# KMO_IO_MV2_5.net
KiCad netlist of a schematic drawn in EAGLE
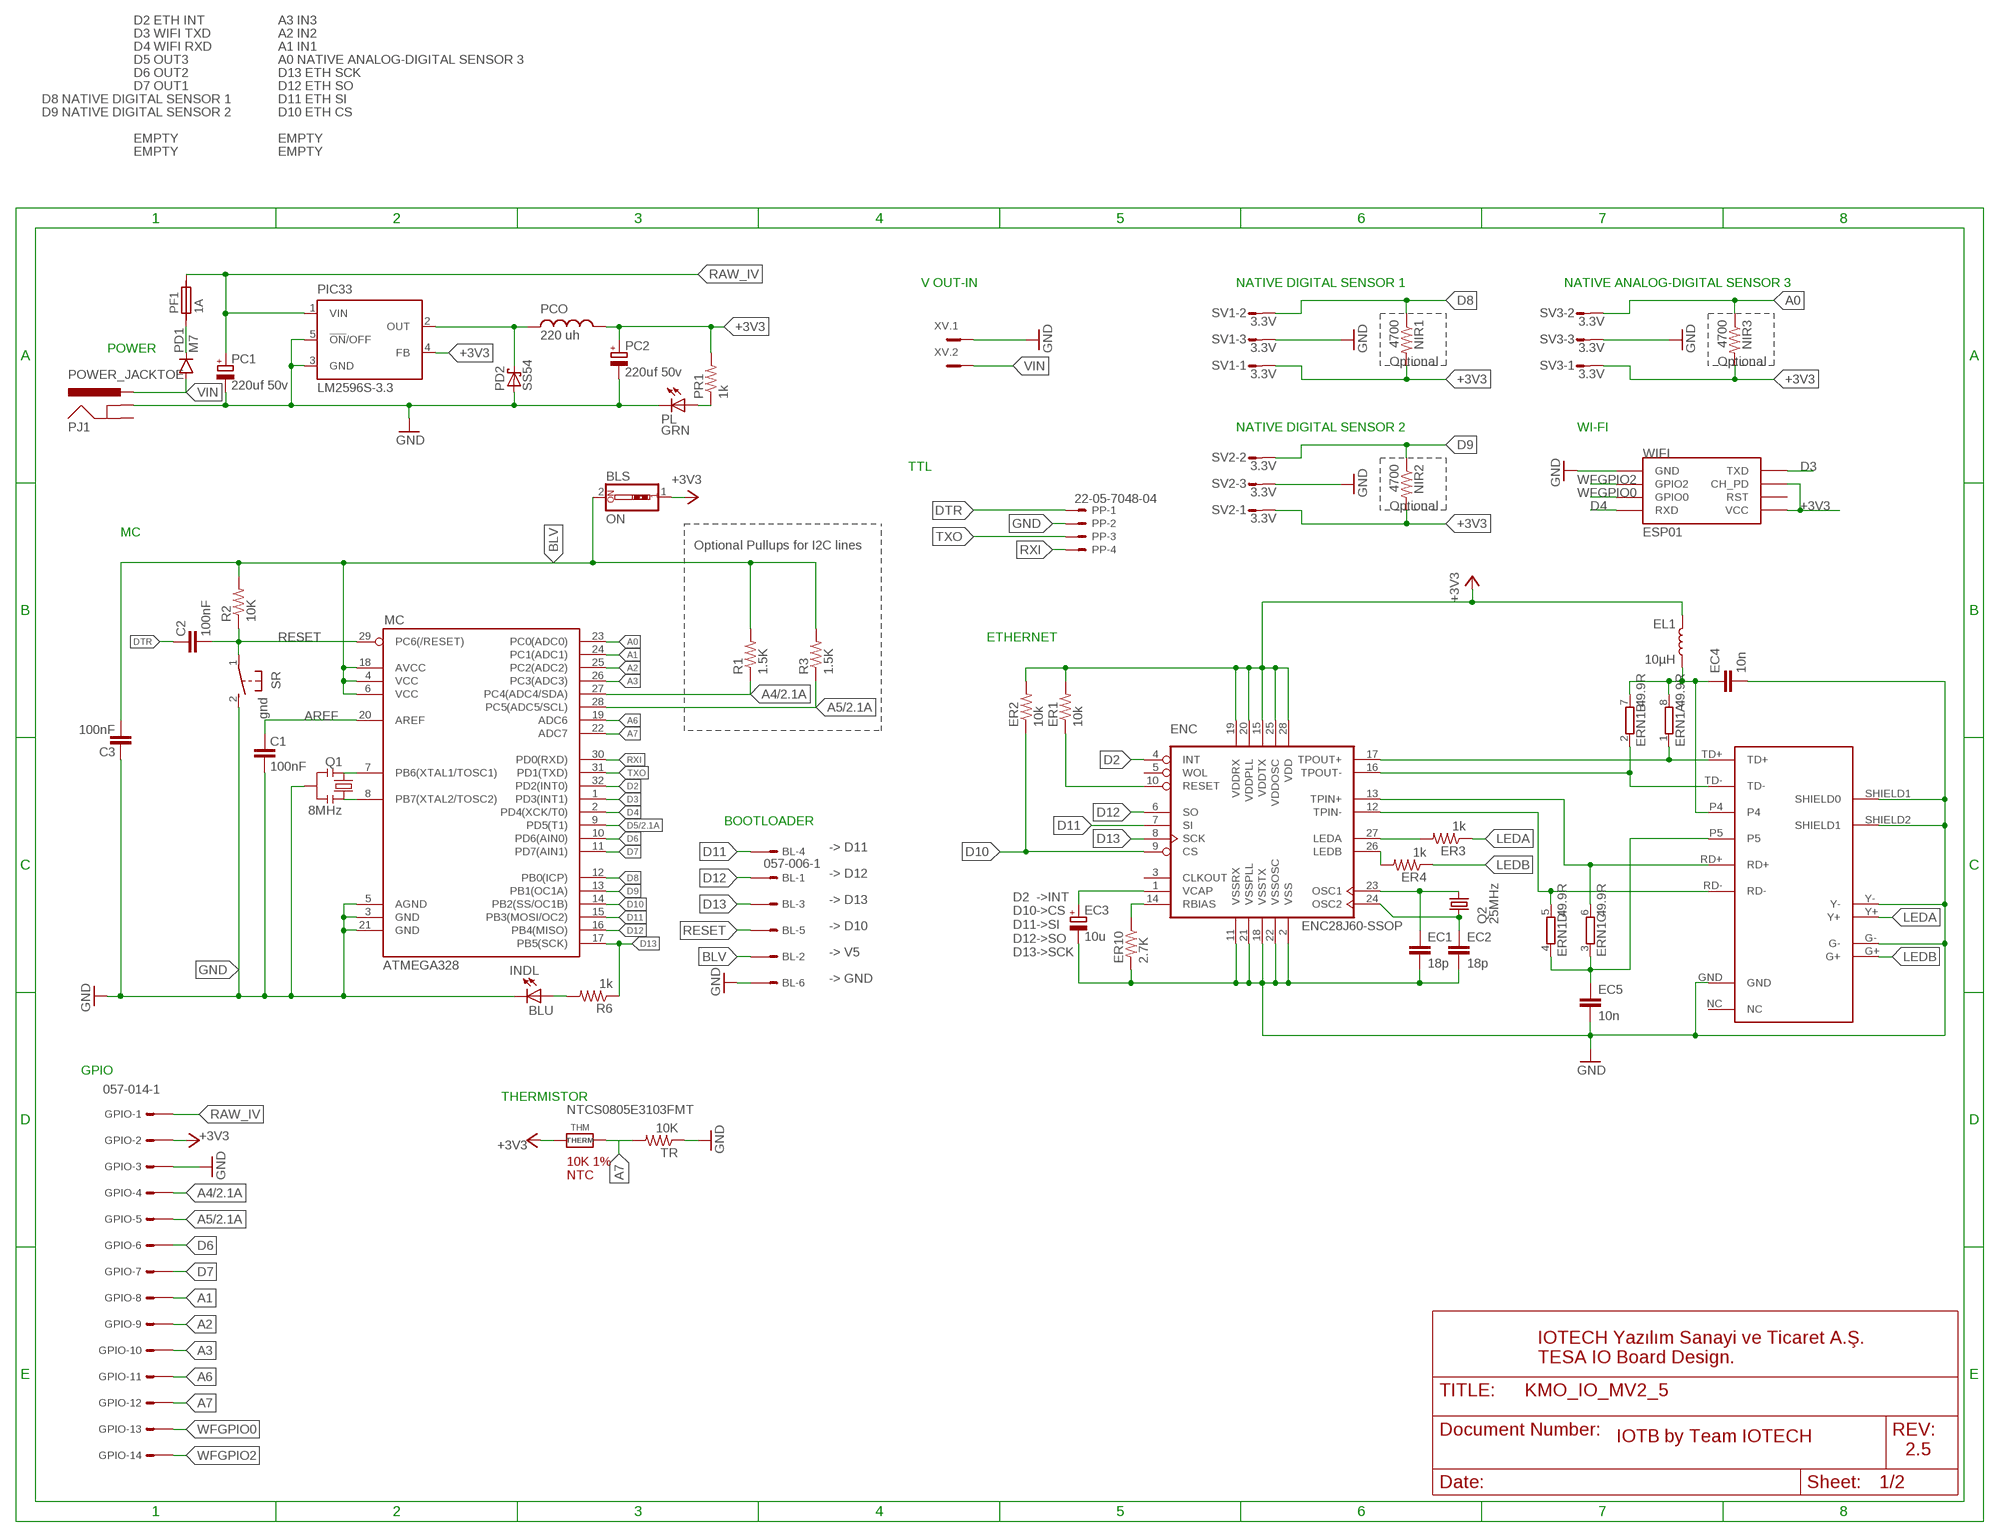
[diagram p0: schematic, sheet 1]
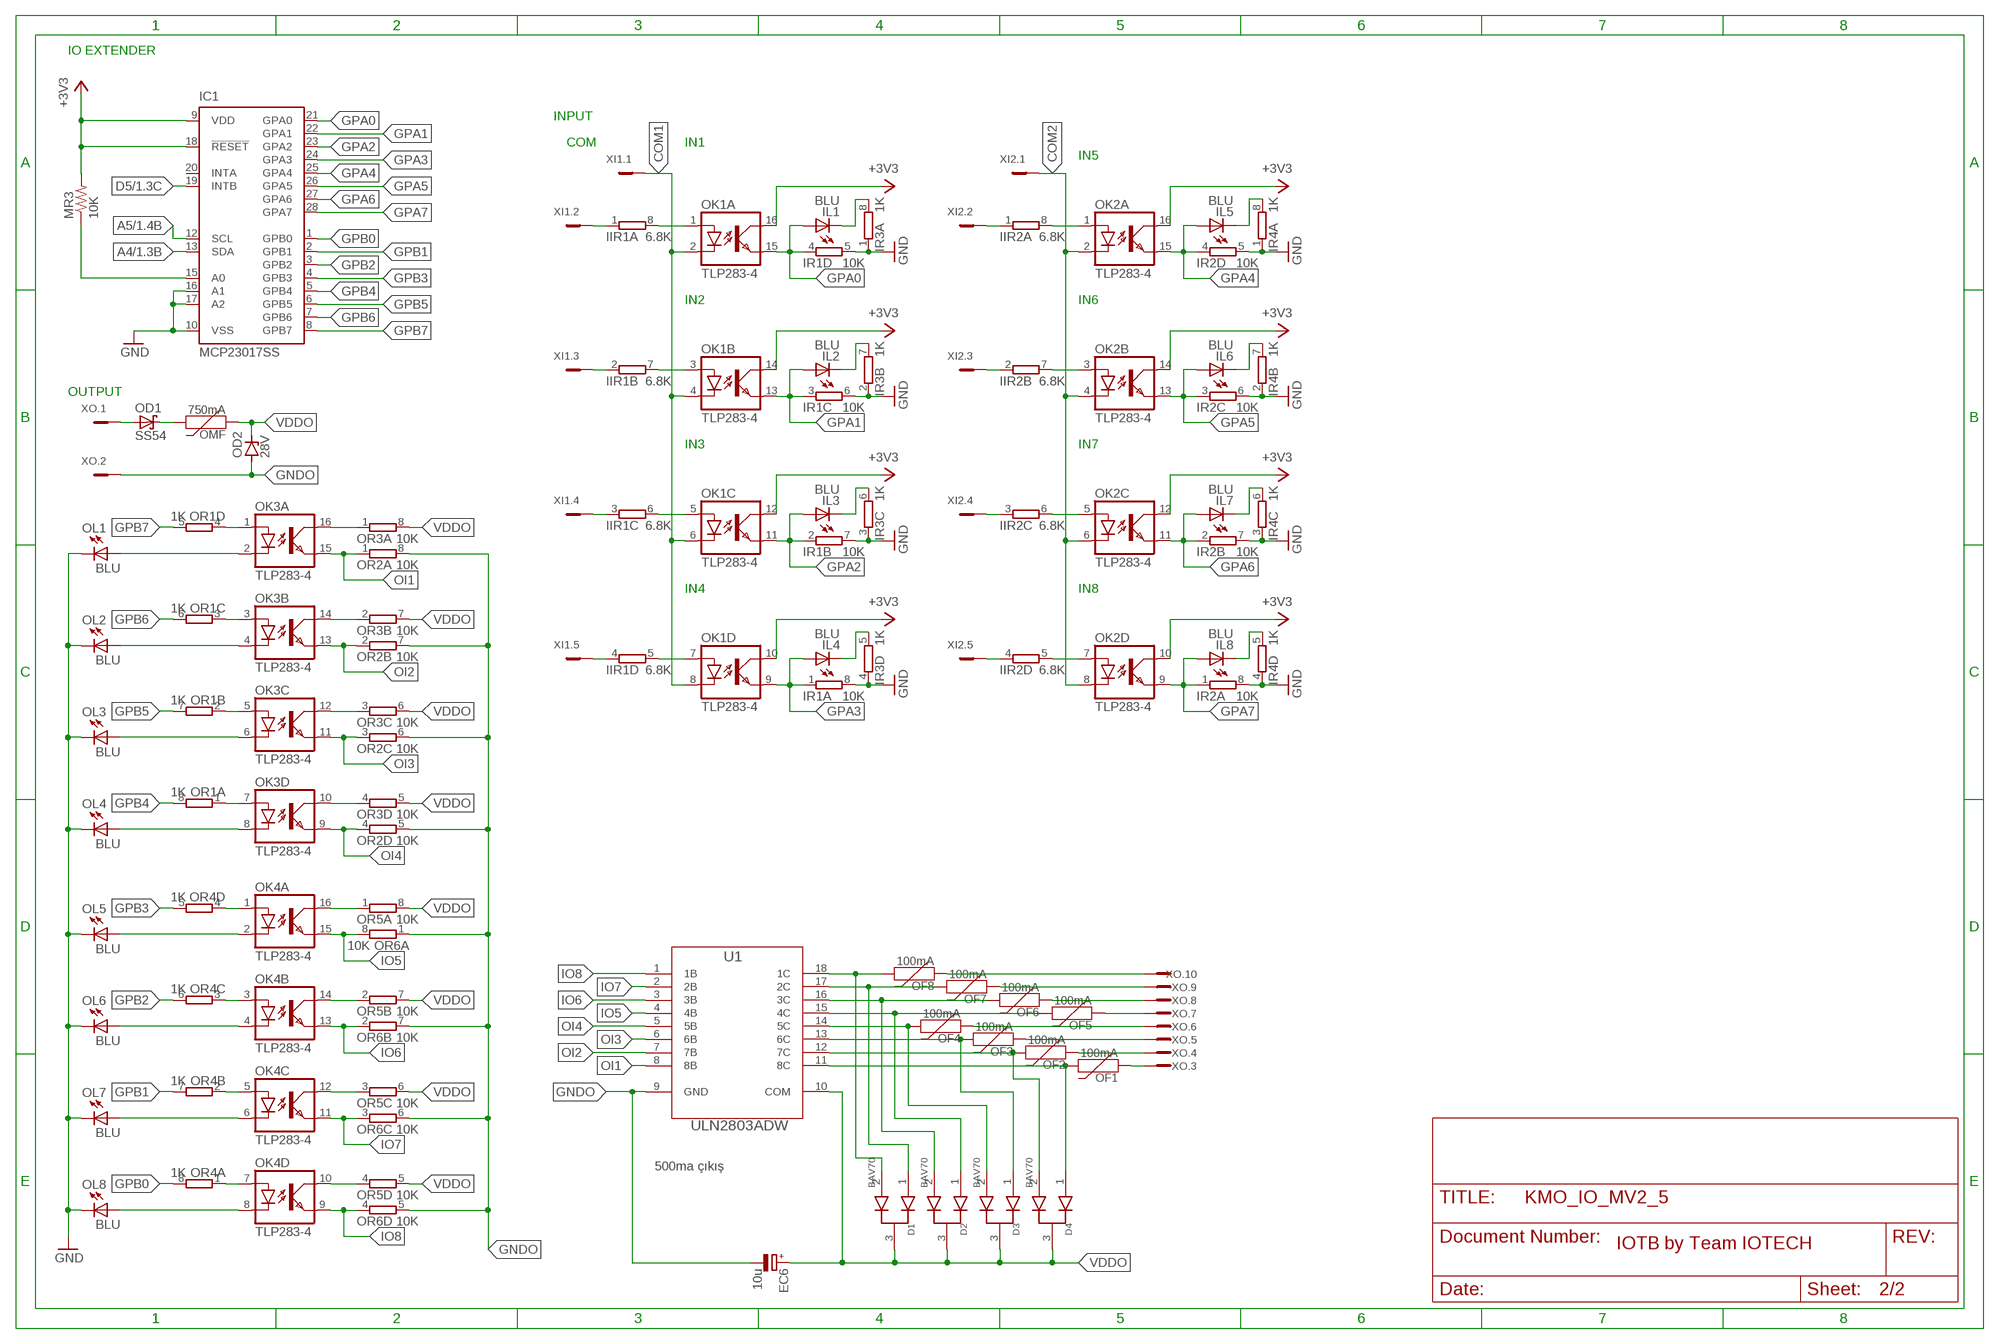
[diagram p1: schematic, sheet 2]

(export (version "E")
  (design (tool "Eeschema 10.0.6"))
  (components
    (comp (ref "D1")
      (value "BAV70")
      (footprint "eagle-import:SOT-23-3")
      (fields (field (name "MF") "Multicomp") (field (name "MP") "BAV70+"))
      (libsource (lib "eagle-import") (part "BAV70"))
    )
    (comp (ref "D2")
      (value "BAV70")
      (footprint "eagle-import:SOT-23-3")
      (fields (field (name "MF") "Multicomp") (field (name "MP") "BAV70+"))
      (libsource (lib "eagle-import") (part "BAV70"))
    )
    (comp (ref "D3")
      (value "BAV70")
      (footprint "eagle-import:SOT-23-3")
      (fields (field (name "MF") "Multicomp") (field (name "MP") "BAV70+"))
      (libsource (lib "eagle-import") (part "BAV70"))
    )
    (comp (ref "D4")
      (value "BAV70")
      (footprint "eagle-import:SOT-23-3")
      (fields (field (name "MF") "Multicomp") (field (name "MP") "BAV70+"))
      (libsource (lib "eagle-import") (part "BAV70"))
    )
    (comp (ref "EC6")
      (value "10u")
      (footprint "eagle-import:CT3216")
      (libsource (lib "eagle-import") (part "CPOL-EUCT3216"))
    )
    (comp (ref "IC1")
      (value "MCP23017SS")
      (footprint "eagle-import:SSOP28")
      (fields (field (name "MF") "MICROCHIP") (field (name "MPN") "MCP23017-E/SS"))
      (libsource (lib "eagle-import") (part "MCP23017SS"))
    )
    (comp (ref "IIR1")
      (value "6.8K")
      (footprint "eagle-import:0603-ARV")
      (libsource (lib "eagle-import") (part "4R-N0603-ARV"))
    )
    (comp (ref "IIR2")
      (value "6.8K")
      (footprint "eagle-import:0603-ARV")
      (libsource (lib "eagle-import") (part "4R-N0603-ARV"))
    )
    (comp (ref "IL1")
      (value "BLU")
      (footprint "eagle-import:CHIP-LED0805")
      (libsource (lib "eagle-import") (part "LEDCHIP-LED0805"))
    )
    (comp (ref "IL2")
      (value "BLU")
      (footprint "eagle-import:CHIP-LED0805")
      (libsource (lib "eagle-import") (part "LEDCHIP-LED0805"))
    )
    (comp (ref "IL3")
      (value "BLU")
      (footprint "eagle-import:CHIP-LED0805")
      (libsource (lib "eagle-import") (part "LEDCHIP-LED0805"))
    )
    (comp (ref "IL4")
      (value "BLU")
      (footprint "eagle-import:CHIP-LED0805")
      (libsource (lib "eagle-import") (part "LEDCHIP-LED0805"))
    )
    (comp (ref "IL5")
      (value "BLU")
      (footprint "eagle-import:CHIP-LED0805")
      (libsource (lib "eagle-import") (part "LEDCHIP-LED0805"))
    )
    (comp (ref "IL6")
      (value "BLU")
      (footprint "eagle-import:CHIP-LED0805")
      (libsource (lib "eagle-import") (part "LEDCHIP-LED0805"))
    )
    (comp (ref "IL7")
      (value "BLU")
      (footprint "eagle-import:CHIP-LED0805")
      (libsource (lib "eagle-import") (part "LEDCHIP-LED0805"))
    )
    (comp (ref "IL8")
      (value "BLU")
      (footprint "eagle-import:CHIP-LED0805")
      (libsource (lib "eagle-import") (part "LEDCHIP-LED0805"))
    )
    (comp (ref "IR1")
      (value "10K")
      (footprint "eagle-import:0603-ARV")
      (libsource (lib "eagle-import") (part "4R-N0603-ARV"))
    )
    (comp (ref "IR2")
      (value "10K")
      (footprint "eagle-import:0603-ARV")
      (libsource (lib "eagle-import") (part "4R-N0603-ARV"))
    )
    (comp (ref "IR3")
      (value "1K")
      (footprint "eagle-import:0603-ARV")
      (libsource (lib "eagle-import") (part "4R-N0603-ARV"))
    )
    (comp (ref "IR4")
      (value "1K")
      (footprint "eagle-import:0603-ARV")
      (libsource (lib "eagle-import") (part "4R-N0603-ARV"))
    )
    (comp (ref "MR3")
      (value "10K")
      (footprint "eagle-import:0805")
      (libsource (lib "eagle-import") (part "RESISTOR0805-RES"))
    )
    (comp (ref "OD1")
      (value "SS54")
      (footprint "eagle-import:SMB")
      (libsource (lib "eagle-import") (part "SCHOTTKY-DIODESMD"))
    )
    (comp (ref "OD2")
      (value "28V")
      (footprint "eagle-import:SMB")
      (libsource (lib "eagle-import") (part "ZENER-DIODESMB"))
    )
    (comp (ref "OF1")
      (value "100mA")
      (footprint "eagle-import:1206")
      (libsource (lib "eagle-import") (part "PPTC_0.75A"))
    )
    (comp (ref "OF2")
      (value "100mA")
      (footprint "eagle-import:1206")
      (libsource (lib "eagle-import") (part "PPTC_0.75A"))
    )
    (comp (ref "OF3")
      (value "100mA")
      (footprint "eagle-import:1206")
      (libsource (lib "eagle-import") (part "PPTC_0.75A"))
    )
    (comp (ref "OF4")
      (value "100mA")
      (footprint "eagle-import:1206")
      (libsource (lib "eagle-import") (part "PPTC_0.75A"))
    )
    (comp (ref "OF5")
      (value "100mA")
      (footprint "eagle-import:1206")
      (libsource (lib "eagle-import") (part "PPTC_0.75A"))
    )
    (comp (ref "OF6")
      (value "100mA")
      (footprint "eagle-import:1206")
      (libsource (lib "eagle-import") (part "PPTC_0.75A"))
    )
    (comp (ref "OF7")
      (value "100mA")
      (footprint "eagle-import:1206")
      (libsource (lib "eagle-import") (part "PPTC_0.75A"))
    )
    (comp (ref "OF8")
      (value "100mA")
      (footprint "eagle-import:1206")
      (libsource (lib "eagle-import") (part "PPTC_0.75A"))
    )
    (comp (ref "OK1")
      (value "TLP283-4")
      (footprint "eagle-import:MINI-FLAT-16")
      (fields (field (name "SPICEPREFIX") "O"))
      (libsource (lib "eagle-import") (part "TLP283-4"))
    )
    (comp (ref "OK2")
      (value "TLP283-4")
      (footprint "eagle-import:MINI-FLAT-16")
      (fields (field (name "SPICEPREFIX") "O"))
      (libsource (lib "eagle-import") (part "TLP283-4"))
    )
    (comp (ref "OK3")
      (value "TLP283-4")
      (footprint "eagle-import:MINI-FLAT-16")
      (libsource (lib "eagle-import") (part "TLP283-4"))
    )
    (comp (ref "OK4")
      (value "TLP283-4")
      (footprint "eagle-import:MINI-FLAT-16")
      (libsource (lib "eagle-import") (part "TLP283-4"))
    )
    (comp (ref "OL1")
      (value "BLU")
      (footprint "eagle-import:CHIP-LED0805")
      (libsource (lib "eagle-import") (part "LEDCHIP-LED0805"))
    )
    (comp (ref "OL2")
      (value "BLU")
      (footprint "eagle-import:CHIP-LED0805")
      (libsource (lib "eagle-import") (part "LEDCHIP-LED0805"))
    )
    (comp (ref "OL3")
      (value "BLU")
      (footprint "eagle-import:CHIP-LED0805")
      (libsource (lib "eagle-import") (part "LEDCHIP-LED0805"))
    )
    (comp (ref "OL4")
      (value "BLU")
      (footprint "eagle-import:CHIP-LED0805")
      (libsource (lib "eagle-import") (part "LEDCHIP-LED0805"))
    )
    (comp (ref "OL5")
      (value "BLU")
      (footprint "eagle-import:CHIP-LED0805")
      (libsource (lib "eagle-import") (part "LEDCHIP-LED0805"))
    )
    (comp (ref "OL6")
      (value "BLU")
      (footprint "eagle-import:CHIP-LED0805")
      (libsource (lib "eagle-import") (part "LEDCHIP-LED0805"))
    )
    (comp (ref "OL7")
      (value "BLU")
      (footprint "eagle-import:CHIP-LED0805")
      (libsource (lib "eagle-import") (part "LEDCHIP-LED0805"))
    )
    (comp (ref "OL8")
      (value "BLU")
      (footprint "eagle-import:CHIP-LED0805")
      (libsource (lib "eagle-import") (part "LEDCHIP-LED0805"))
    )
    (comp (ref "OMF")
      (value "750mA")
      (footprint "eagle-import:1206")
      (libsource (lib "eagle-import") (part "PPTC_0.75A"))
    )
    (comp (ref "OR1")
      (value "1K")
      (footprint "eagle-import:0603-ARV")
      (libsource (lib "eagle-import") (part "4R-N0603-ARV"))
    )
    (comp (ref "OR2")
      (value "10K")
      (footprint "eagle-import:0603-ARV")
      (libsource (lib "eagle-import") (part "4R-N0603-ARV"))
    )
    (comp (ref "OR3")
      (value "10K")
      (footprint "eagle-import:0603-ARV")
      (libsource (lib "eagle-import") (part "4R-N0603-ARV"))
    )
    (comp (ref "OR4")
      (value "1K")
      (footprint "eagle-import:0603-ARV")
      (libsource (lib "eagle-import") (part "4R-N0603-ARV"))
    )
    (comp (ref "OR5")
      (value "10K")
      (footprint "eagle-import:0603-ARV")
      (libsource (lib "eagle-import") (part "4R-N0603-ARV"))
    )
    (comp (ref "OR6")
      (value "10K")
      (footprint "eagle-import:0603-ARV")
      (libsource (lib "eagle-import") (part "4R-N0603-ARV"))
    )
    (comp (ref "U1")
      (value "ULN2803ADW")
      (footprint "eagle-import:SOIC127P1030X265-18N")
      (libsource (lib "eagle-import") (part "ULN2803ADW"))
    )
    (comp (ref "XI1")
      (value "MC5")
      (footprint "eagle-import:MC5")
      (libsource (lib "eagle-import") (part "MC5"))
    )
    (comp (ref "XI2")
      (value "MC5")
      (footprint "eagle-import:MC5")
      (libsource (lib "eagle-import") (part "MC5"))
    )
    (comp (ref "XO")
      (value "MC10")
      (footprint "eagle-import:MC10")
      (libsource (lib "eagle-import") (part "MC10"))
    )
    (comp (ref "BL")
      (value "057-006-1")
      (footprint "eagle-import:057-006-1")
      (libsource (lib "eagle-import") (part "057-006-1"))
    )
    (comp (ref "BLS")
      (value "ON")
      (footprint "eagle-import:EDG-01")
      (libsource (lib "eagle-import") (part "SW_DIP-1"))
    )
    (comp (ref "C1")
      (value "100nF")
      (footprint "eagle-import:0805")
      (libsource (lib "eagle-import") (part "CAP0805"))
    )
    (comp (ref "C2")
      (value "100nF")
      (footprint "eagle-import:0805")
      (libsource (lib "eagle-import") (part "CAP0805"))
    )
    (comp (ref "C3")
      (value "100nF")
      (footprint "eagle-import:0805")
      (libsource (lib "eagle-import") (part "CAP0805"))
    )
    (comp (ref "EC1")
      (value "18p")
      (footprint "eagle-import:0805")
      (libsource (lib "eagle-import") (part "CAP0805"))
    )
    (comp (ref "EC2")
      (value "18p")
      (footprint "eagle-import:0805")
      (libsource (lib "eagle-import") (part "CAP0805"))
    )
    (comp (ref "EC3")
      (value "10u")
      (footprint "eagle-import:CT3216")
      (libsource (lib "eagle-import") (part "CPOL-EUCT3216"))
    )
    (comp (ref "EC4")
      (value "10n")
      (footprint "eagle-import:0805")
      (libsource (lib "eagle-import") (part "CAP0805"))
    )
    (comp (ref "EC5")
      (value "10n")
      (footprint "eagle-import:0805")
      (libsource (lib "eagle-import") (part "CAP0805"))
    )
    (comp (ref "EL1")
      (value "10µH")
      (footprint "eagle-import:0805")
      (libsource (lib "eagle-import") (part "INDUCTOR-0805-3.3UH"))
    )
    (comp (ref "ENC")
      (value "ENC28J60-SSOP")
      (footprint "eagle-import:SSOP28")
      (libsource (lib "eagle-import") (part "ENC28J60-SSOP"))
    )
    (comp (ref "ER1")
      (value "10k")
      (footprint "eagle-import:0805")
      (libsource (lib "eagle-import") (part "RESISTOR0805-RES"))
    )
    (comp (ref "ER2")
      (value "10k")
      (footprint "eagle-import:0805")
      (libsource (lib "eagle-import") (part "RESISTOR0805-RES"))
    )
    (comp (ref "ER3")
      (value "1k")
      (footprint "eagle-import:0805")
      (libsource (lib "eagle-import") (part "RESISTOR0805-RES"))
    )
    (comp (ref "ER4")
      (value "1k")
      (footprint "eagle-import:0805")
      (libsource (lib "eagle-import") (part "RESISTOR0805-RES"))
    )
    (comp (ref "ER10")
      (value "2.7K")
      (footprint "eagle-import:0805")
      (libsource (lib "eagle-import") (part "RESISTOR0805-RES"))
    )
    (comp (ref "ERN1")
      (value "49.9R")
      (footprint "eagle-import:0603-ARV")
      (libsource (lib "eagle-import") (part "4R-N0603-ARV"))
    )
    (comp (ref "GPIO")
      (value "057-014-1")
      (footprint "eagle-import:057-014-1")
      (libsource (lib "eagle-import") (part "057-014-1"))
    )
    (comp (ref "INDL")
      (value "BLU")
      (footprint "eagle-import:CHIP-LED0805")
      (libsource (lib "eagle-import") (part "LEDCHIP-LED0805"))
    )
    (comp (ref "MC")
      (value "ATMEGA328")
      (footprint "eagle-import:TQFP32-08")
      (libsource (lib "eagle-import") (part "ATMEGA168"))
    )
    (comp (ref "NIR1")
      (value "4700")
      (footprint "eagle-import:0805")
      (libsource (lib "eagle-import") (part "RESISTOR0805-RES"))
    )
    (comp (ref "NIR2")
      (value "4700")
      (footprint "eagle-import:0805")
      (libsource (lib "eagle-import") (part "RESISTOR0805-RES"))
    )
    (comp (ref "NIR3")
      (value "4700")
      (footprint "eagle-import:0805")
      (libsource (lib "eagle-import") (part "RESISTOR0805-RES"))
    )
    (comp (ref "PC1")
      (value "220uf 50v")
      (footprint "eagle-import:140CLH-1010")
      (libsource (lib "eagle-import") (part "CPOL-EU140CLH-1010"))
    )
    (comp (ref "PC2")
      (value "220uf 50v")
      (footprint "eagle-import:140CLH-1010")
      (libsource (lib "eagle-import") (part "CPOL-EU140CLH-1010"))
    )
    (comp (ref "PCO")
      (value "220 uh")
      (footprint "eagle-import:MSS1260")
      (libsource (lib "eagle-import") (part "MSS1260"))
    )
    (comp (ref "PD1")
      (value "M7")
      (footprint "eagle-import:SMA-DIODE")
      (libsource (lib "eagle-import") (part "DIODESMA"))
    )
    (comp (ref "PD2")
      (value "SS54")
      (footprint "eagle-import:SMB")
      (libsource (lib "eagle-import") (part "SCHOTTKY-DIODESMD"))
    )
    (comp (ref "PF1")
      (value "1A")
      (footprint "eagle-import:1820")
      (libsource (lib "eagle-import") (part "SIBA194600"))
    )
    (comp (ref "PIC33")
      (value "LM2596S-3.3")
      (footprint "eagle-import:TO263-5")
      (fields
        (field (name "MF") "NATIONAL SEMICONDUCTOR")
        (field (name "MPN") "LM2596S-ADJ/NOPB")
        (field (name "SPICEPREFIX") "X")
      )
      (libsource (lib "eagle-import") (part "LM2596S"))
    )
    (comp (ref "PJ1")
      (value "POWER_JACKTOE")
      (footprint "eagle-import:POWER_JACK_SMD_OVERPASTE_TOE")
      (libsource (lib "eagle-import") (part "POWER_JACKTOE"))
    )
    (comp (ref "PL")
      (value "GRN")
      (footprint "eagle-import:CHIP-LED0805")
      (libsource (lib "eagle-import") (part "LEDCHIP-LED0805"))
    )
    (comp (ref "PP")
      (value "22-05-7048-04")
      (footprint "eagle-import:7395-04")
      (fields (field (name "MF") "MOLEX"))
      (libsource (lib "eagle-import") (part "22-?-0405-7048"))
    )
    (comp (ref "PR1")
      (value "1k")
      (footprint "eagle-import:0805")
      (libsource (lib "eagle-import") (part "RESISTOR0805-RES"))
    )
    (comp (ref "Q1")
      (value "8MHz")
      (footprint "eagle-import:RESONATOR-SMD-1_1")
      (libsource (lib "eagle-import") (part "RESONATOR1{colon}1"))
    )
    (comp (ref "Q2")
      (value "25MHz")
      (footprint "eagle-import:5.0X3.2_2")
      (libsource (lib "eagle-import") (part "KX-9B"))
    )
    (comp (ref "R1")
      (value "1.5K")
      (footprint "eagle-import:0805")
      (libsource (lib "eagle-import") (part "RESISTOR0805-RES"))
    )
    (comp (ref "R2")
      (value "10K")
      (footprint "eagle-import:0805")
      (libsource (lib "eagle-import") (part "RESISTOR0805-RES"))
    )
    (comp (ref "R3")
      (value "1.5K")
      (footprint "eagle-import:0805")
      (libsource (lib "eagle-import") (part "RESISTOR0805-RES"))
    )
    (comp (ref "R6")
      (value "1k")
      (footprint "eagle-import:0805")
      (libsource (lib "eagle-import") (part "RESISTOR0805-RES"))
    )
    (comp (ref "SR")
      (value "gnd")
      (footprint "eagle-import:B3F-31XX")
      (fields (field (name "MPN") "B3F-3100"))
      (libsource (lib "eagle-import") (part "31-XX"))
    )
    (comp (ref "SV1")
      (value "3.3V")
      (footprint "eagle-import:S03P")
      (libsource (lib "eagle-import") (part "S03P"))
    )
    (comp (ref "SV2")
      (value "3.3V")
      (footprint "eagle-import:S03P")
      (libsource (lib "eagle-import") (part "S03P"))
    )
    (comp (ref "SV3")
      (value "3.3V")
      (footprint "eagle-import:S03P")
      (libsource (lib "eagle-import") (part "S03P"))
    )
    (comp (ref "THM")
      (value "THERM")
      (footprint "eagle-import:MICROBUILDER_0805_NOTHERMALS")
      (libsource (lib "eagle-import") (part "MICROBUILDER_RESISTOR0805_NOTHERMALS"))
    )
    (comp (ref "TR")
      (value "10K")
      (footprint "eagle-import:0805")
      (libsource (lib "eagle-import") (part "RESISTOR0805-RES"))
    )
    (comp (ref "U$2")
      (value "HR911105A")
      (footprint "eagle-import:RJ45")
      (libsource (lib "eagle-import") (part "HR911105A"))
    )
    (comp (ref "WIFI")
      (value "ESP01")
      (footprint "eagle-import:ESP01")
      (libsource (lib "eagle-import") (part "ESP01"))
    )
    (comp (ref "XV")
      (value "MC2")
      (footprint "eagle-import:MC2")
      (libsource (lib "eagle-import") (part "MC2"))
    )
  )
  (nets
    (net (code "1") (name "+3V3") (class "Default")
      (node (ref "BLS") (pin "1") (pinfunction "1_1") (pintype "passive"))
      (node (ref "EL1") (pin "1") (pinfunction "1_1") (pintype "passive"))
      (node (ref "ENC") (pin "15") (pinfunction "VDDTX_15") (pintype "power_in"))
      (node (ref "ENC") (pin "19") (pinfunction "VDDRX_19") (pintype "power_in"))
      (node (ref "ENC") (pin "20") (pinfunction "VDDPLL_20") (pintype "power_in"))
      (node (ref "ENC") (pin "25") (pinfunction "VDDOSC_25") (pintype "power_in"))
      (node (ref "ENC") (pin "28") (pinfunction "VDD_28") (pintype "power_in"))
      (node (ref "ER1") (pin "2") (pinfunction "2_2") (pintype "passive"))
      (node (ref "ER2") (pin "2") (pinfunction "2_2") (pintype "passive"))
      (node (ref "GPIO") (pin "2") (pinfunction "S_2") (pintype "passive"))
      (node (ref "IC1") (pin "18") (pinfunction "~{RESET}_18") (pintype "input"))
      (node (ref "IC1") (pin "9") (pinfunction "VDD_9") (pintype "power_in"))
      (node (ref "MR3") (pin "2") (pinfunction "2_2") (pintype "passive"))
      (node (ref "NIR1") (pin "2") (pinfunction "2_2") (pintype "passive"))
      (node (ref "NIR2") (pin "2") (pinfunction "2_2") (pintype "passive"))
      (node (ref "NIR3") (pin "2") (pinfunction "2_2") (pintype "passive"))
      (node (ref "OK1") (pin "10") (pinfunction "COL_10") (pintype "passive"))
      (node (ref "OK1") (pin "12") (pinfunction "COL_12") (pintype "passive"))
      (node (ref "OK1") (pin "14") (pinfunction "COL_14") (pintype "passive"))
      (node (ref "OK1") (pin "16") (pinfunction "COL_16") (pintype "passive"))
      (node (ref "OK2") (pin "10") (pinfunction "COL_10") (pintype "passive"))
      (node (ref "OK2") (pin "12") (pinfunction "COL_12") (pintype "passive"))
      (node (ref "OK2") (pin "14") (pinfunction "COL_14") (pintype "passive"))
      (node (ref "OK2") (pin "16") (pinfunction "COL_16") (pintype "passive"))
      (node (ref "PC2") (pin "+") (pinfunction "+_+") (pintype "passive"))
      (node (ref "PCO") (pin "P$1") (pinfunction "P$1_P$1") (pintype "passive"))
      (node (ref "PIC33") (pin "4") (pinfunction "FB_4") (pintype "input"))
      (node (ref "PR1") (pin "2") (pinfunction "2_2") (pintype "passive"))
      (node (ref "SV1") (pin "1") (pinfunction "S_1") (pintype "passive"))
      (node (ref "SV2") (pin "1") (pinfunction "S_1") (pintype "passive"))
      (node (ref "SV3") (pin "1") (pinfunction "S_1") (pintype "passive"))
      (node (ref "THM") (pin "1") (pinfunction "1_1") (pintype "passive"))
      (node (ref "WIFI") (pin "CH_PD") (pinfunction "CH_PD_CH_PD") (pintype "bidirectional"))
      (node (ref "WIFI") (pin "VCC") (pinfunction "VCC_VCC") (pintype "bidirectional"))
    )
    (net (code "2") (name "A0") (class "Default")
      (node (ref "MC") (pin "23") (pinfunction "PC0(ADC0)_23") (pintype "bidirectional"))
      (node (ref "NIR3") (pin "1") (pinfunction "1_1") (pintype "passive"))
      (node (ref "SV3") (pin "2") (pinfunction "S_2") (pintype "passive"))
    )
    (net (code "3") (name "A1") (class "Default")
      (node (ref "GPIO") (pin "8") (pinfunction "S_8") (pintype "passive"))
      (node (ref "MC") (pin "24") (pinfunction "PC1(ADC1)_24") (pintype "bidirectional"))
    )
    (net (code "4") (name "A2") (class "Default")
      (node (ref "GPIO") (pin "9") (pinfunction "S_9") (pintype "passive"))
      (node (ref "MC") (pin "25") (pinfunction "PC2(ADC2)_25") (pintype "bidirectional"))
    )
    (net (code "5") (name "A3") (class "Default")
      (node (ref "GPIO") (pin "10") (pinfunction "S_10") (pintype "passive"))
      (node (ref "MC") (pin "26") (pinfunction "PC3(ADC3)_26") (pintype "bidirectional"))
    )
    (net (code "6") (name "A4") (class "Default")
      (node (ref "GPIO") (pin "4") (pinfunction "S_4") (pintype "passive"))
      (node (ref "IC1") (pin "13") (pinfunction "SDA_13") (pintype "bidirectional"))
      (node (ref "MC") (pin "27") (pinfunction "PC4(ADC4/SDA)_27") (pintype "bidirectional"))
      (node (ref "R1") (pin "1") (pinfunction "1_1") (pintype "passive"))
    )
    (net (code "7") (name "A5") (class "Default")
      (node (ref "GPIO") (pin "5") (pinfunction "S_5") (pintype "passive"))
      (node (ref "IC1") (pin "12") (pinfunction "SCL_12") (pintype "input"))
      (node (ref "MC") (pin "28") (pinfunction "PC5(ADC5/SCL)_28") (pintype "bidirectional"))
      (node (ref "R3") (pin "1") (pinfunction "1_1") (pintype "passive"))
    )
    (net (code "8") (name "A6") (class "Default")
      (node (ref "GPIO") (pin "11") (pinfunction "S_11") (pintype "passive"))
      (node (ref "MC") (pin "19") (pinfunction "ADC6_19") (pintype "bidirectional"))
    )
    (net (code "9") (name "A7") (class "Default")
      (node (ref "GPIO") (pin "12") (pinfunction "S_12") (pintype "passive"))
      (node (ref "MC") (pin "22") (pinfunction "ADC7_22") (pintype "bidirectional"))
      (node (ref "THM") (pin "2") (pinfunction "2_2") (pintype "passive"))
      (node (ref "TR") (pin "2") (pinfunction "2_2") (pintype "passive"))
    )
    (net (code "10") (name "AREF") (class "Default")
      (node (ref "C1") (pin "2") (pinfunction "2_2") (pintype "passive"))
      (node (ref "MC") (pin "20") (pinfunction "AREF_20") (pintype "bidirectional"))
    )
    (net (code "11") (name "BLV") (class "Default")
      (node (ref "BL") (pin "2") (pinfunction "S_2") (pintype "passive"))
      (node (ref "BLS") (pin "2") (pinfunction "2_2") (pintype "passive"))
      (node (ref "C3") (pin "1") (pinfunction "1_1") (pintype "passive"))
      (node (ref "MC") (pin "18") (pinfunction "AVCC_18") (pintype "bidirectional"))
      (node (ref "MC") (pin "4") (pinfunction "VCC_4") (pintype "bidirectional"))
      (node (ref "MC") (pin "6") (pinfunction "VCC_6") (pintype "bidirectional"))
      (node (ref "R1") (pin "2") (pinfunction "2_2") (pintype "passive"))
      (node (ref "R2") (pin "2") (pinfunction "2_2") (pintype "passive"))
      (node (ref "R3") (pin "2") (pinfunction "2_2") (pintype "passive"))
    )
    (net (code "12") (name "COM1") (class "Default")
      (node (ref "OK1") (pin "2") (pinfunction "C_2") (pintype "passive"))
      (node (ref "OK1") (pin "4") (pinfunction "C_4") (pintype "passive"))
      (node (ref "OK1") (pin "6") (pinfunction "C_6") (pintype "passive"))
      (node (ref "OK1") (pin "8") (pinfunction "C_8") (pintype "passive"))
      (node (ref "XI1") (pin "1") (pinfunction "SK_1") (pintype "passive"))
    )
    (net (code "13") (name "COM2") (class "Default")
      (node (ref "OK2") (pin "2") (pinfunction "C_2") (pintype "passive"))
      (node (ref "OK2") (pin "4") (pinfunction "C_4") (pintype "passive"))
      (node (ref "OK2") (pin "6") (pinfunction "C_6") (pintype "passive"))
      (node (ref "OK2") (pin "8") (pinfunction "C_8") (pintype "passive"))
      (node (ref "XI2") (pin "1") (pinfunction "SK_1") (pintype "passive"))
    )
    (net (code "14") (name "D2") (class "Default")
      (node (ref "ENC") (pin "4") (pinfunction "INT_4") (pintype "output"))
      (node (ref "MC") (pin "32") (pinfunction "PD2(INT0)_32") (pintype "bidirectional"))
    )
    (net (code "15") (name "D3") (class "Default")
      (node (ref "MC") (pin "1") (pinfunction "PD3(INT1)_1") (pintype "bidirectional"))
      (node (ref "WIFI") (pin "TX") (pinfunction "TXD_TX") (pintype "bidirectional"))
    )
    (net (code "16") (name "D4") (class "Default")
      (node (ref "MC") (pin "2") (pinfunction "PD4(XCK/T0)_2") (pintype "bidirectional"))
      (node (ref "WIFI") (pin "RX") (pinfunction "RXD_RX") (pintype "bidirectional"))
    )
    (net (code "17") (name "D5") (class "Default")
      (node (ref "IC1") (pin "19") (pinfunction "INTB_19") (pintype "output"))
      (node (ref "MC") (pin "9") (pinfunction "PD5(T1)_9") (pintype "bidirectional"))
    )
    (net (code "18") (name "D6") (class "Default")
      (node (ref "GPIO") (pin "6") (pinfunction "S_6") (pintype "passive"))
      (node (ref "MC") (pin "10") (pinfunction "PD6(AIN0)_10") (pintype "bidirectional"))
    )
    (net (code "19") (name "D7") (class "Default")
      (node (ref "GPIO") (pin "7") (pinfunction "S_7") (pintype "passive"))
      (node (ref "MC") (pin "11") (pinfunction "PD7(AIN1)_11") (pintype "bidirectional"))
    )
    (net (code "20") (name "D8") (class "Default")
      (node (ref "MC") (pin "12") (pinfunction "PB0(ICP)_12") (pintype "bidirectional"))
      (node (ref "NIR1") (pin "1") (pinfunction "1_1") (pintype "passive"))
      (node (ref "SV1") (pin "2") (pinfunction "S_2") (pintype "passive"))
    )
    (net (code "21") (name "D9") (class "Default")
      (node (ref "MC") (pin "13") (pinfunction "PB1(OC1A)_13") (pintype "bidirectional"))
      (node (ref "NIR2") (pin "1") (pinfunction "1_1") (pintype "passive"))
      (node (ref "SV2") (pin "2") (pinfunction "S_2") (pintype "passive"))
    )
    (net (code "22") (name "D10") (class "Default")
      (node (ref "ENC") (pin "9") (pinfunction "CS_9") (pintype "input"))
      (node (ref "ER2") (pin "1") (pinfunction "1_1") (pintype "passive"))
      (node (ref "MC") (pin "14") (pinfunction "PB2(SS/OC1B)_14") (pintype "bidirectional"))
    )
    (net (code "23") (name "D11") (class "Default")
      (node (ref "BL") (pin "4") (pinfunction "S_4") (pintype "passive"))
      (node (ref "ENC") (pin "7") (pinfunction "SI_7") (pintype "input"))
      (node (ref "MC") (pin "15") (pinfunction "PB3(MOSI/OC2)_15") (pintype "bidirectional"))
    )
    (net (code "24") (name "D12") (class "Default")
      (node (ref "BL") (pin "1") (pinfunction "S_1") (pintype "passive"))
      (node (ref "ENC") (pin "6") (pinfunction "SO_6") (pintype "output"))
      (node (ref "MC") (pin "16") (pinfunction "PB4(MISO)_16") (pintype "bidirectional"))
    )
    (net (code "25") (name "D13") (class "Default")
      (node (ref "BL") (pin "3") (pinfunction "S_3") (pintype "passive"))
      (node (ref "ENC") (pin "8") (pinfunction "SCK_8") (pintype "input"))
      (node (ref "MC") (pin "17") (pinfunction "PB5(SCK)_17") (pintype "bidirectional"))
      (node (ref "R6") (pin "1") (pinfunction "1_1") (pintype "passive"))
    )
    (net (code "26") (name "DTR") (class "Default")
      (node (ref "C2") (pin "2") (pinfunction "2_2") (pintype "passive"))
      (node (ref "PP") (pin "1") (pinfunction "S_1") (pintype "passive"))
    )
    (net (code "27") (name "GND") (class "Default")
      (node (ref "BL") (pin "6") (pinfunction "S_6") (pintype "passive"))
      (node (ref "C1") (pin "1") (pinfunction "1_1") (pintype "passive"))
      (node (ref "C3") (pin "2") (pinfunction "2_2") (pintype "passive"))
      (node (ref "EC1") (pin "2") (pinfunction "2_2") (pintype "passive"))
      (node (ref "EC2") (pin "2") (pinfunction "2_2") (pintype "passive"))
      (node (ref "EC3") (pin "-") (pinfunction "-_-") (pintype "passive"))
      (node (ref "EC4") (pin "2") (pinfunction "2_2") (pintype "passive"))
      (node (ref "EC5") (pin "2") (pinfunction "2_2") (pintype "passive"))
      (node (ref "ENC") (pin "11") (pinfunction "VSSRX_11") (pintype "power_in"))
      (node (ref "ENC") (pin "18") (pinfunction "VSSTX_18") (pintype "power_in"))
      (node (ref "ENC") (pin "2") (pinfunction "VSS_2") (pintype "power_in"))
      (node (ref "ENC") (pin "21") (pinfunction "VSSPLL_21") (pintype "power_in"))
      (node (ref "ENC") (pin "22") (pinfunction "VSSOSC_22") (pintype "power_in"))
      (node (ref "ER10") (pin "2") (pinfunction "2_2") (pintype "passive"))
      (node (ref "GPIO") (pin "3") (pinfunction "S_3") (pintype "passive"))
      (node (ref "IC1") (pin "10") (pinfunction "VSS_10") (pintype "power_in"))
      (node (ref "IC1") (pin "16") (pinfunction "A1_16") (pintype "input"))
      (node (ref "IC1") (pin "17") (pinfunction "A2_17") (pintype "input"))
      (node (ref "INDL") (pin "C") (pinfunction "C_C") (pintype "passive"))
      (node (ref "IR1") (pin "5") (pinfunction "2_5") (pintype "passive"))
      (node (ref "IR1") (pin "6") (pinfunction "2_6") (pintype "passive"))
      (node (ref "IR1") (pin "7") (pinfunction "2_7") (pintype "passive"))
      (node (ref "IR1") (pin "8") (pinfunction "2_8") (pintype "passive"))
      (node (ref "IR2") (pin "5") (pinfunction "2_5") (pintype "passive"))
      (node (ref "IR2") (pin "6") (pinfunction "2_6") (pintype "passive"))
      (node (ref "IR2") (pin "7") (pinfunction "2_7") (pintype "passive"))
      (node (ref "IR2") (pin "8") (pinfunction "2_8") (pintype "passive"))
      (node (ref "IR3") (pin "1") (pinfunction "1_1") (pintype "passive"))
      (node (ref "IR3") (pin "2") (pinfunction "1_2") (pintype "passive"))
      (node (ref "IR3") (pin "3") (pinfunction "1_3") (pintype "passive"))
      (node (ref "IR3") (pin "4") (pinfunction "1_4") (pintype "passive"))
      (node (ref "IR4") (pin "1") (pinfunction "1_1") (pintype "passive"))
      (node (ref "IR4") (pin "2") (pinfunction "1_2") (pintype "passive"))
      (node (ref "IR4") (pin "3") (pinfunction "1_3") (pintype "passive"))
      (node (ref "IR4") (pin "4") (pinfunction "1_4") (pintype "passive"))
      (node (ref "MC") (pin "21") (pinfunction "GND_21") (pintype "bidirectional"))
      (node (ref "MC") (pin "3") (pinfunction "GND_3") (pintype "bidirectional"))
      (node (ref "MC") (pin "5") (pinfunction "AGND_5") (pintype "bidirectional"))
      (node (ref "OL1") (pin "C") (pinfunction "C_C") (pintype "passive"))
      (node (ref "OL2") (pin "C") (pinfunction "C_C") (pintype "passive"))
      (node (ref "OL3") (pin "C") (pinfunction "C_C") (pintype "passive"))
      (node (ref "OL4") (pin "C") (pinfunction "C_C") (pintype "passive"))
      (node (ref "OL5") (pin "C") (pinfunction "C_C") (pintype "passive"))
      (node (ref "OL6") (pin "C") (pinfunction "C_C") (pintype "passive"))
      (node (ref "OL7") (pin "C") (pinfunction "C_C") (pintype "passive"))
      (node (ref "OL8") (pin "C") (pinfunction "C_C") (pintype "passive"))
      (node (ref "PC1") (pin "-") (pinfunction "-_-") (pintype "passive"))
      (node (ref "PC2") (pin "-") (pinfunction "-_-") (pintype "passive"))
      (node (ref "PD2") (pin "A") (pinfunction "A_A") (pintype "passive"))
      (node (ref "PIC33") (pin "3") (pinfunction "GND_3") (pintype "power_in"))
      (node (ref "PIC33") (pin "5") (pinfunction "~{ON}/OFF_5") (pintype "input"))
      (node (ref "PJ1") (pin "GND") (pinfunction "GNDBREAK_GND") (pintype "bidirectional"))
      (node (ref "PL") (pin "C") (pinfunction "C_C") (pintype "passive"))
      (node (ref "PP") (pin "2") (pinfunction "S_2") (pintype "passive"))
      (node (ref "Q1") (pin "2") (pinfunction "2_2") (pintype "passive"))
      (node (ref "SR") (pin "2") (pinfunction "S_2") (pintype "passive"))
      (node (ref "SV1") (pin "3") (pinfunction "S_3") (pintype "passive"))
      (node (ref "SV2") (pin "3") (pinfunction "S_3") (pintype "passive"))
      (node (ref "SV3") (pin "3") (pinfunction "S_3") (pintype "passive"))
      (node (ref "TR") (pin "1") (pinfunction "1_1") (pintype "passive"))
      (node (ref "U$2") (pin "G-") (pinfunction "G-_G-") (pintype "bidirectional"))
      (node (ref "U$2") (pin "GND") (pinfunction "GND_GND") (pintype "bidirectional"))
      (node (ref "U$2") (pin "SHIELD1") (pinfunction "SHIELD0_SHIELD1") (pintype "bidirectional"))
      (node (ref "U$2") (pin "SHIELD2") (pinfunction "SHIELD1_SHIELD2") (pintype "bidirectional"))
      (node (ref "U$2") (pin "Y-") (pinfunction "Y-_Y-") (pintype "bidirectional"))
      (node (ref "WIFI") (pin "GND") (pinfunction "GND_GND") (pintype "bidirectional"))
      (node (ref "XV") (pin "1") (pinfunction "SK_1") (pintype "passive"))
    )
    (net (code "28") (name "GNDO") (class "Default")
      (node (ref "EC6") (pin "-") (pinfunction "-_-") (pintype "passive"))
      (node (ref "OD2") (pin "A") (pinfunction "A_A") (pintype "passive"))
      (node (ref "OR2") (pin "5") (pinfunction "2_5") (pintype "passive"))
      (node (ref "OR2") (pin "6") (pinfunction "2_6") (pintype "passive"))
      (node (ref "OR2") (pin "7") (pinfunction "2_7") (pintype "passive"))
      (node (ref "OR2") (pin "8") (pinfunction "2_8") (pintype "passive"))
      (node (ref "OR6") (pin "1") (pinfunction "1_1") (pintype "passive"))
      (node (ref "OR6") (pin "5") (pinfunction "2_5") (pintype "passive"))
      (node (ref "OR6") (pin "6") (pinfunction "2_6") (pintype "passive"))
      (node (ref "OR6") (pin "7") (pinfunction "2_7") (pintype "passive"))
      (node (ref "U1") (pin "9") (pinfunction "GND_9") (pintype "passive"))
      (node (ref "XO") (pin "2") (pinfunction "SK_2") (pintype "passive"))
    )
    (net (code "29") (name "GPA0") (class "Default")
      (node (ref "IC1") (pin "21") (pinfunction "GPA0_21") (pintype "bidirectional"))
      (node (ref "IL1") (pin "A") (pinfunction "A_A") (pintype "passive"))
      (node (ref "IR1") (pin "4") (pinfunction "1_4") (pintype "passive"))
      (node (ref "OK1") (pin "15") (pinfunction "EMIT_15") (pintype "passive"))
    )
    (net (code "30") (name "GPA1") (class "Default")
      (node (ref "IC1") (pin "22") (pinfunction "GPA1_22") (pintype "bidirectional"))
      (node (ref "IL2") (pin "A") (pinfunction "A_A") (pintype "passive"))
      (node (ref "IR1") (pin "3") (pinfunction "1_3") (pintype "passive"))
      (node (ref "OK1") (pin "13") (pinfunction "EMIT_13") (pintype "passive"))
    )
    (net (code "31") (name "GPA2") (class "Default")
      (node (ref "IC1") (pin "23") (pinfunction "GPA2_23") (pintype "bidirectional"))
      (node (ref "IL3") (pin "A") (pinfunction "A_A") (pintype "passive"))
      (node (ref "IR1") (pin "2") (pinfunction "1_2") (pintype "passive"))
      (node (ref "OK1") (pin "11") (pinfunction "EMIT_11") (pintype "passive"))
    )
    (net (code "32") (name "GPA3") (class "Default")
      (node (ref "IC1") (pin "24") (pinfunction "GPA3_24") (pintype "bidirectional"))
      (node (ref "IL4") (pin "A") (pinfunction "A_A") (pintype "passive"))
      (node (ref "IR1") (pin "1") (pinfunction "1_1") (pintype "passive"))
      (node (ref "OK1") (pin "9") (pinfunction "EMIT_9") (pintype "passive"))
    )
    (net (code "33") (name "GPA4") (class "Default")
      (node (ref "IC1") (pin "25") (pinfunction "GPA4_25") (pintype "bidirectional"))
      (node (ref "IL5") (pin "A") (pinfunction "A_A") (pintype "passive"))
      (node (ref "IR2") (pin "4") (pinfunction "1_4") (pintype "passive"))
      (node (ref "OK2") (pin "15") (pinfunction "EMIT_15") (pintype "passive"))
    )
    (net (code "34") (name "GPA5") (class "Default")
      (node (ref "IC1") (pin "26") (pinfunction "GPA5_26") (pintype "bidirectional"))
      (node (ref "IL6") (pin "A") (pinfunction "A_A") (pintype "passive"))
      (node (ref "IR2") (pin "3") (pinfunction "1_3") (pintype "passive"))
      (node (ref "OK2") (pin "13") (pinfunction "EMIT_13") (pintype "passive"))
    )
    (net (code "35") (name "GPA6") (class "Default")
      (node (ref "IC1") (pin "27") (pinfunction "GPA6_27") (pintype "bidirectional"))
      (node (ref "IL7") (pin "A") (pinfunction "A_A") (pintype "passive"))
      (node (ref "IR2") (pin "2") (pinfunction "1_2") (pintype "passive"))
      (node (ref "OK2") (pin "11") (pinfunction "EMIT_11") (pintype "passive"))
    )
    (net (code "36") (name "GPA7") (class "Default")
      (node (ref "IC1") (pin "28") (pinfunction "GPA7_28") (pintype "bidirectional"))
      (node (ref "IL8") (pin "A") (pinfunction "A_A") (pintype "passive"))
      (node (ref "IR2") (pin "1") (pinfunction "1_1") (pintype "passive"))
      (node (ref "OK2") (pin "9") (pinfunction "EMIT_9") (pintype "passive"))
    )
    (net (code "37") (name "GPB0") (class "Default")
      (node (ref "IC1") (pin "1") (pinfunction "GPB0_1") (pintype "bidirectional"))
      (node (ref "OR4") (pin "8") (pinfunction "2_8") (pintype "passive"))
    )
    (net (code "38") (name "GPB1") (class "Default")
      (node (ref "IC1") (pin "2") (pinfunction "GPB1_2") (pintype "bidirectional"))
      (node (ref "OR4") (pin "7") (pinfunction "2_7") (pintype "passive"))
    )
    (net (code "39") (name "GPB2") (class "Default")
      (node (ref "IC1") (pin "3") (pinfunction "GPB2_3") (pintype "bidirectional"))
      (node (ref "OR4") (pin "6") (pinfunction "2_6") (pintype "passive"))
    )
    (net (code "40") (name "GPB3") (class "Default")
      (node (ref "IC1") (pin "4") (pinfunction "GPB3_4") (pintype "bidirectional"))
      (node (ref "OR4") (pin "5") (pinfunction "2_5") (pintype "passive"))
    )
    (net (code "41") (name "GPB4") (class "Default")
      (node (ref "IC1") (pin "5") (pinfunction "GPB4_5") (pintype "bidirectional"))
      (node (ref "OR1") (pin "8") (pinfunction "2_8") (pintype "passive"))
    )
    (net (code "42") (name "GPB5") (class "Default")
      (node (ref "IC1") (pin "6") (pinfunction "GPB5_6") (pintype "bidirectional"))
      (node (ref "OR1") (pin "7") (pinfunction "2_7") (pintype "passive"))
    )
    (net (code "43") (name "GPB6") (class "Default")
      (node (ref "IC1") (pin "7") (pinfunction "GPB6_7") (pintype "bidirectional"))
      (node (ref "OR1") (pin "6") (pinfunction "2_6") (pintype "passive"))
    )
    (net (code "44") (name "GPB7") (class "Default")
      (node (ref "IC1") (pin "8") (pinfunction "GPB7_8") (pintype "bidirectional"))
      (node (ref "OR1") (pin "5") (pinfunction "2_5") (pintype "passive"))
    )
    (net (code "45") (name "IO5") (class "Default")
      (node (ref "OK4") (pin "15") (pinfunction "EMIT_15") (pintype "passive"))
      (node (ref "OR6") (pin "8") (pinfunction "2_8") (pintype "passive"))
      (node (ref "U1") (pin "4") (pinfunction "4B_4") (pintype "input"))
    )
    (net (code "46") (name "IO6") (class "Default")
      (node (ref "OK4") (pin "13") (pinfunction "EMIT_13") (pintype "passive"))
      (node (ref "OR6") (pin "2") (pinfunction "1_2") (pintype "passive"))
      (node (ref "U1") (pin "3") (pinfunction "3B_3") (pintype "input"))
    )
    (net (code "47") (name "IO7") (class "Default")
      (node (ref "OK4") (pin "11") (pinfunction "EMIT_11") (pintype "passive"))
      (node (ref "OR6") (pin "3") (pinfunction "1_3") (pintype "passive"))
      (node (ref "U1") (pin "2") (pinfunction "2B_2") (pintype "input"))
    )
    (net (code "48") (name "IO8") (class "Default")
      (node (ref "OK4") (pin "9") (pinfunction "EMIT_9") (pintype "passive"))
      (node (ref "OR6") (pin "4") (pinfunction "1_4") (pintype "passive"))
      (node (ref "U1") (pin "1") (pinfunction "1B_1") (pintype "input"))
    )
    (net (code "49") (name "LEDA") (class "Default")
      (node (ref "ER3") (pin "1") (pinfunction "1_1") (pintype "passive"))
      (node (ref "U$2") (pin "Y+") (pinfunction "Y+_Y+") (pintype "bidirectional"))
    )
    (net (code "50") (name "LEDB") (class "Default")
      (node (ref "ER4") (pin "1") (pinfunction "1_1") (pintype "passive"))
      (node (ref "U$2") (pin "G+") (pinfunction "G+_G+") (pintype "bidirectional"))
    )
    (net (code "51") (name "Net-(ENC-LEDA)") (class "Default")
      (node (ref "ENC") (pin "27") (pinfunction "LEDA_27") (pintype "output"))
      (node (ref "ER3") (pin "2") (pinfunction "2_2") (pintype "passive"))
    )
    (net (code "52") (name "Net-(ENC-LEDB)") (class "Default")
      (node (ref "ENC") (pin "26") (pinfunction "LEDB_26") (pintype "output"))
      (node (ref "ER4") (pin "2") (pinfunction "2_2") (pintype "passive"))
    )
    (net (code "53") (name "Net-(ENC-OSC1)") (class "Default")
      (node (ref "EC1") (pin "1") (pinfunction "1_1") (pintype "passive"))
      (node (ref "ENC") (pin "23") (pinfunction "OSC1_23") (pintype "input"))
      (node (ref "Q2") (pin "2") (pinfunction "2_2") (pintype "passive"))
    )
    (net (code "54") (name "Net-(ENC-OSC2)") (class "Default")
      (node (ref "EC2") (pin "1") (pinfunction "1_1") (pintype "passive"))
      (node (ref "ENC") (pin "24") (pinfunction "OSC2_24") (pintype "output"))
      (node (ref "Q2") (pin "1") (pinfunction "1_1") (pintype "passive"))
    )
    (net (code "55") (name "Net-(ENC-RBIAS)") (class "Default")
      (node (ref "ENC") (pin "14") (pinfunction "RBIAS_14") (pintype "passive"))
      (node (ref "ER10") (pin "1") (pinfunction "1_1") (pintype "passive"))
    )
    (net (code "56") (name "Net-(ENC-RESET)") (class "Default")
      (node (ref "ENC") (pin "10") (pinfunction "RESET_10") (pintype "input"))
      (node (ref "ER1") (pin "1") (pinfunction "1_1") (pintype "passive"))
    )
    (net (code "57") (name "Net-(ENC-TPIN+)") (class "Default")
      (node (ref "ENC") (pin "13") (pinfunction "TPIN+_13") (pintype "input"))
      (node (ref "ERN1") (pin "6") (pinfunction "2_6") (pintype "passive"))
      (node (ref "U$2") (pin "RD+") (pinfunction "RD+_RD+") (pintype "bidirectional"))
    )
    (net (code "58") (name "Net-(ENC-TPIN-)") (class "Default")
      (node (ref "ENC") (pin "12") (pinfunction "TPIN-_12") (pintype "input"))
      (node (ref "ERN1") (pin "5") (pinfunction "2_5") (pintype "passive"))
      (node (ref "U$2") (pin "RD-") (pinfunction "RD-_RD-") (pintype "bidirectional"))
    )
    (net (code "59") (name "Net-(ENC-TPOUT+)") (class "Default")
      (node (ref "ENC") (pin "17") (pinfunction "TPOUT+_17") (pintype "output"))
      (node (ref "ERN1") (pin "1") (pinfunction "1_1") (pintype "passive"))
      (node (ref "U$2") (pin "TD+") (pinfunction "TD+_TD+") (pintype "bidirectional"))
    )
    (net (code "60") (name "Net-(ENC-TPOUT-)") (class "Default")
      (node (ref "ENC") (pin "16") (pinfunction "TPOUT-_16") (pintype "output"))
      (node (ref "ERN1") (pin "2") (pinfunction "1_2") (pintype "passive"))
      (node (ref "U$2") (pin "TD-") (pinfunction "TD-_TD-") (pintype "bidirectional"))
    )
    (net (code "61") (name "Net-(ENC-VCAP)") (class "Default")
      (node (ref "EC3") (pin "+") (pinfunction "+_+") (pintype "passive"))
      (node (ref "ENC") (pin "1") (pinfunction "VCAP_1") (pintype "power_in"))
    )
    (net (code "62") (name "Net-(ERN1A-2)") (class "Default")
      (node (ref "EC4") (pin "1") (pinfunction "1_1") (pintype "passive"))
      (node (ref "EL1") (pin "2") (pinfunction "2_2") (pintype "passive"))
      (node (ref "ERN1") (pin "7") (pinfunction "2_7") (pintype "passive"))
      (node (ref "ERN1") (pin "8") (pinfunction "2_8") (pintype "passive"))
      (node (ref "U$2") (pin "P4") (pinfunction "P4_P4") (pintype "bidirectional"))
    )
    (net (code "63") (name "Net-(ERN1C-1)") (class "Default")
      (node (ref "EC5") (pin "1") (pinfunction "1_1") (pintype "passive"))
      (node (ref "ERN1") (pin "3") (pinfunction "1_3") (pintype "passive"))
      (node (ref "ERN1") (pin "4") (pinfunction "1_4") (pintype "passive"))
      (node (ref "U$2") (pin "P5") (pinfunction "P5_P5") (pintype "bidirectional"))
    )
    (net (code "64") (name "Net-(IC1-A0)") (class "Default")
      (node (ref "IC1") (pin "15") (pinfunction "A0_15") (pintype "input"))
      (node (ref "MR3") (pin "1") (pinfunction "1_1") (pintype "passive"))
    )
    (net (code "65") (name "Net-(IIR1A-2)") (class "Default")
      (node (ref "IIR1") (pin "8") (pinfunction "2_8") (pintype "passive"))
      (node (ref "OK1") (pin "1") (pinfunction "A_1") (pintype "passive"))
    )
    (net (code "66") (name "Net-(IIR1B-1)") (class "Default")
      (node (ref "IIR1") (pin "2") (pinfunction "1_2") (pintype "passive"))
      (node (ref "XI1") (pin "3") (pinfunction "SK_3") (pintype "passive"))
    )
    (net (code "67") (name "Net-(IIR1B-2)") (class "Default")
      (node (ref "IIR1") (pin "7") (pinfunction "2_7") (pintype "passive"))
      (node (ref "OK1") (pin "3") (pinfunction "A_3") (pintype "passive"))
    )
    (net (code "68") (name "Net-(IIR1C-1)") (class "Default")
      (node (ref "IIR1") (pin "3") (pinfunction "1_3") (pintype "passive"))
      (node (ref "XI1") (pin "4") (pinfunction "SK_4") (pintype "passive"))
    )
    (net (code "69") (name "Net-(IIR1C-2)") (class "Default")
      (node (ref "IIR1") (pin "6") (pinfunction "2_6") (pintype "passive"))
      (node (ref "OK1") (pin "5") (pinfunction "A_5") (pintype "passive"))
    )
    (net (code "70") (name "Net-(IIR1D-1)") (class "Default")
      (node (ref "IIR1") (pin "4") (pinfunction "1_4") (pintype "passive"))
      (node (ref "XI1") (pin "5") (pinfunction "SK_5") (pintype "passive"))
    )
    (net (code "71") (name "Net-(IIR1D-2)") (class "Default")
      (node (ref "IIR1") (pin "5") (pinfunction "2_5") (pintype "passive"))
      (node (ref "OK1") (pin "7") (pinfunction "A_7") (pintype "passive"))
    )
    (net (code "72") (name "Net-(IIR2A-2)") (class "Default")
      (node (ref "IIR2") (pin "8") (pinfunction "2_8") (pintype "passive"))
      (node (ref "OK2") (pin "1") (pinfunction "A_1") (pintype "passive"))
    )
    (net (code "73") (name "Net-(IIR2B-1)") (class "Default")
      (node (ref "IIR2") (pin "2") (pinfunction "1_2") (pintype "passive"))
      (node (ref "XI2") (pin "3") (pinfunction "SK_3") (pintype "passive"))
    )
    (net (code "74") (name "Net-(IIR2B-2)") (class "Default")
      (node (ref "IIR2") (pin "7") (pinfunction "2_7") (pintype "passive"))
      (node (ref "OK2") (pin "3") (pinfunction "A_3") (pintype "passive"))
    )
    (net (code "75") (name "Net-(IIR2C-1)") (class "Default")
      (node (ref "IIR2") (pin "3") (pinfunction "1_3") (pintype "passive"))
      (node (ref "XI2") (pin "4") (pinfunction "SK_4") (pintype "passive"))
    )
    (net (code "76") (name "Net-(IIR2C-2)") (class "Default")
      (node (ref "IIR2") (pin "6") (pinfunction "2_6") (pintype "passive"))
      (node (ref "OK2") (pin "5") (pinfunction "A_5") (pintype "passive"))
    )
    (net (code "77") (name "Net-(IIR2D-1)") (class "Default")
      (node (ref "IIR2") (pin "4") (pinfunction "1_4") (pintype "passive"))
      (node (ref "XI2") (pin "5") (pinfunction "SK_5") (pintype "passive"))
    )
    (net (code "78") (name "Net-(IIR2D-2)") (class "Default")
      (node (ref "IIR2") (pin "5") (pinfunction "2_5") (pintype "passive"))
      (node (ref "OK2") (pin "7") (pinfunction "A_7") (pintype "passive"))
    )
    (net (code "79") (name "Net-(INDL-PadA)") (class "Default")
      (node (ref "INDL") (pin "A") (pinfunction "A_A") (pintype "passive"))
      (node (ref "R6") (pin "2") (pinfunction "2_2") (pintype "passive"))
    )
    (net (code "80") (name "Net-(IR3A-2)") (class "Default")
      (node (ref "IL1") (pin "C") (pinfunction "C_C") (pintype "passive"))
      (node (ref "IR3") (pin "8") (pinfunction "2_8") (pintype "passive"))
    )
    (net (code "81") (name "Net-(IR3B-2)") (class "Default")
      (node (ref "IL2") (pin "C") (pinfunction "C_C") (pintype "passive"))
      (node (ref "IR3") (pin "7") (pinfunction "2_7") (pintype "passive"))
    )
    (net (code "82") (name "Net-(IR3C-2)") (class "Default")
      (node (ref "IL3") (pin "C") (pinfunction "C_C") (pintype "passive"))
      (node (ref "IR3") (pin "6") (pinfunction "2_6") (pintype "passive"))
    )
    (net (code "83") (name "Net-(IR3D-2)") (class "Default")
      (node (ref "IL4") (pin "C") (pinfunction "C_C") (pintype "passive"))
      (node (ref "IR3") (pin "5") (pinfunction "2_5") (pintype "passive"))
    )
    (net (code "84") (name "Net-(IR4A-2)") (class "Default")
      (node (ref "IL5") (pin "C") (pinfunction "C_C") (pintype "passive"))
      (node (ref "IR4") (pin "8") (pinfunction "2_8") (pintype "passive"))
    )
    (net (code "85") (name "Net-(IR4B-2)") (class "Default")
      (node (ref "IL6") (pin "C") (pinfunction "C_C") (pintype "passive"))
      (node (ref "IR4") (pin "7") (pinfunction "2_7") (pintype "passive"))
    )
    (net (code "86") (name "Net-(IR4C-2)") (class "Default")
      (node (ref "IL7") (pin "C") (pinfunction "C_C") (pintype "passive"))
      (node (ref "IR4") (pin "6") (pinfunction "2_6") (pintype "passive"))
    )
    (net (code "87") (name "Net-(IR4D-2)") (class "Default")
      (node (ref "IL8") (pin "C") (pinfunction "C_C") (pintype "passive"))
      (node (ref "IR4") (pin "5") (pinfunction "2_5") (pintype "passive"))
    )
    (net (code "88") (name "Net-(MC-PB6(XTAL1{slash}TOSC1))") (class "Default")
      (node (ref "MC") (pin "7") (pinfunction "PB6(XTAL1/TOSC1)_7") (pintype "bidirectional"))
      (node (ref "Q1") (pin "1") (pinfunction "1_1") (pintype "passive"))
    )
    (net (code "89") (name "Net-(MC-PB7(XTAL2{slash}TOSC2))") (class "Default")
      (node (ref "MC") (pin "8") (pinfunction "PB7(XTAL2/TOSC2)_8") (pintype "bidirectional"))
      (node (ref "Q1") (pin "3") (pinfunction "3_3") (pintype "passive"))
    )
    (net (code "90") (name "Net-(OD1-PadC)") (class "Default")
      (node (ref "OD1") (pin "C") (pinfunction "C_C") (pintype "passive"))
      (node (ref "OMF") (pin "2") (pinfunction "2_2") (pintype "bidirectional"))
    )
    (net (code "91") (name "Net-(OK3A-A)") (class "Default")
      (node (ref "OK3") (pin "1") (pinfunction "A_1") (pintype "passive"))
      (node (ref "OR1") (pin "4") (pinfunction "1_4") (pintype "passive"))
    )
    (net (code "92") (name "Net-(OK3A-C)") (class "Default")
      (node (ref "OK3") (pin "2") (pinfunction "C_2") (pintype "passive"))
      (node (ref "OL1") (pin "A") (pinfunction "A_A") (pintype "passive"))
    )
    (net (code "93") (name "Net-(OK3A-COL)") (class "Default")
      (node (ref "OK3") (pin "16") (pinfunction "COL_16") (pintype "passive"))
      (node (ref "OR3") (pin "1") (pinfunction "1_1") (pintype "passive"))
    )
    (net (code "94") (name "Net-(OK3B-A)") (class "Default")
      (node (ref "OK3") (pin "3") (pinfunction "A_3") (pintype "passive"))
      (node (ref "OR1") (pin "3") (pinfunction "1_3") (pintype "passive"))
    )
    (net (code "95") (name "Net-(OK3B-C)") (class "Default")
      (node (ref "OK3") (pin "4") (pinfunction "C_4") (pintype "passive"))
      (node (ref "OL2") (pin "A") (pinfunction "A_A") (pintype "passive"))
    )
    (net (code "96") (name "Net-(OK3B-COL)") (class "Default")
      (node (ref "OK3") (pin "14") (pinfunction "COL_14") (pintype "passive"))
      (node (ref "OR3") (pin "2") (pinfunction "1_2") (pintype "passive"))
    )
    (net (code "97") (name "Net-(OK3C-A)") (class "Default")
      (node (ref "OK3") (pin "5") (pinfunction "A_5") (pintype "passive"))
      (node (ref "OR1") (pin "2") (pinfunction "1_2") (pintype "passive"))
    )
    (net (code "98") (name "Net-(OK3C-C)") (class "Default")
      (node (ref "OK3") (pin "6") (pinfunction "C_6") (pintype "passive"))
      (node (ref "OL3") (pin "A") (pinfunction "A_A") (pintype "passive"))
    )
    (net (code "99") (name "Net-(OK3C-COL)") (class "Default")
      (node (ref "OK3") (pin "12") (pinfunction "COL_12") (pintype "passive"))
      (node (ref "OR3") (pin "3") (pinfunction "1_3") (pintype "passive"))
    )
    (net (code "100") (name "Net-(OK3D-A)") (class "Default")
      (node (ref "OK3") (pin "7") (pinfunction "A_7") (pintype "passive"))
      (node (ref "OR1") (pin "1") (pinfunction "1_1") (pintype "passive"))
    )
    (net (code "101") (name "Net-(OK3D-C)") (class "Default")
      (node (ref "OK3") (pin "8") (pinfunction "C_8") (pintype "passive"))
      (node (ref "OL4") (pin "A") (pinfunction "A_A") (pintype "passive"))
    )
    (net (code "102") (name "Net-(OK3D-COL)") (class "Default")
      (node (ref "OK3") (pin "10") (pinfunction "COL_10") (pintype "passive"))
      (node (ref "OR3") (pin "4") (pinfunction "1_4") (pintype "passive"))
    )
    (net (code "103") (name "Net-(OK4A-A)") (class "Default")
      (node (ref "OK4") (pin "1") (pinfunction "A_1") (pintype "passive"))
      (node (ref "OR4") (pin "4") (pinfunction "1_4") (pintype "passive"))
    )
    (net (code "104") (name "Net-(OK4A-C)") (class "Default")
      (node (ref "OK4") (pin "2") (pinfunction "C_2") (pintype "passive"))
      (node (ref "OL5") (pin "A") (pinfunction "A_A") (pintype "passive"))
    )
    (net (code "105") (name "Net-(OK4A-COL)") (class "Default")
      (node (ref "OK4") (pin "16") (pinfunction "COL_16") (pintype "passive"))
      (node (ref "OR5") (pin "1") (pinfunction "1_1") (pintype "passive"))
    )
    (net (code "106") (name "Net-(OK4B-A)") (class "Default")
      (node (ref "OK4") (pin "3") (pinfunction "A_3") (pintype "passive"))
      (node (ref "OR4") (pin "3") (pinfunction "1_3") (pintype "passive"))
    )
    (net (code "107") (name "Net-(OK4B-C)") (class "Default")
      (node (ref "OK4") (pin "4") (pinfunction "C_4") (pintype "passive"))
      (node (ref "OL6") (pin "A") (pinfunction "A_A") (pintype "passive"))
    )
    (net (code "108") (name "Net-(OK4B-COL)") (class "Default")
      (node (ref "OK4") (pin "14") (pinfunction "COL_14") (pintype "passive"))
      (node (ref "OR5") (pin "2") (pinfunction "1_2") (pintype "passive"))
    )
    (net (code "109") (name "Net-(OK4C-A)") (class "Default")
      (node (ref "OK4") (pin "5") (pinfunction "A_5") (pintype "passive"))
      (node (ref "OR4") (pin "2") (pinfunction "1_2") (pintype "passive"))
    )
    (net (code "110") (name "Net-(OK4C-C)") (class "Default")
      (node (ref "OK4") (pin "6") (pinfunction "C_6") (pintype "passive"))
      (node (ref "OL7") (pin "A") (pinfunction "A_A") (pintype "passive"))
    )
    (net (code "111") (name "Net-(OK4C-COL)") (class "Default")
      (node (ref "OK4") (pin "12") (pinfunction "COL_12") (pintype "passive"))
      (node (ref "OR5") (pin "3") (pinfunction "1_3") (pintype "passive"))
    )
    (net (code "112") (name "Net-(OK4D-A)") (class "Default")
      (node (ref "OK4") (pin "7") (pinfunction "A_7") (pintype "passive"))
      (node (ref "OR4") (pin "1") (pinfunction "1_1") (pintype "passive"))
    )
    (net (code "113") (name "Net-(OK4D-C)") (class "Default")
      (node (ref "OK4") (pin "8") (pinfunction "C_8") (pintype "passive"))
      (node (ref "OL8") (pin "A") (pinfunction "A_A") (pintype "passive"))
    )
    (net (code "114") (name "Net-(OK4D-COL)") (class "Default")
      (node (ref "OK4") (pin "10") (pinfunction "COL_10") (pintype "passive"))
      (node (ref "OR5") (pin "4") (pinfunction "1_4") (pintype "passive"))
    )
    (net (code "115") (name "Net-(PD1-PadC)") (class "Default")
      (node (ref "PD1") (pin "C") (pinfunction "C_C") (pintype "passive"))
      (node (ref "PF1") (pin "1") (pinfunction "1_1") (pintype "passive"))
    )
    (net (code "116") (name "Net-(PIC33-OUT)") (class "Default")
      (node (ref "PCO") (pin "P$2") (pinfunction "P$2_P$2") (pintype "passive"))
      (node (ref "PD2") (pin "C") (pinfunction "C_C") (pintype "passive"))
      (node (ref "PIC33") (pin "2") (pinfunction "OUT_2") (pintype "output"))
    )
    (net (code "117") (name "Net-(PL-PadA)") (class "Default")
      (node (ref "PL") (pin "A") (pinfunction "A_A") (pintype "passive"))
      (node (ref "PR1") (pin "1") (pinfunction "1_1") (pintype "passive"))
    )
    (net (code "118") (name "Net-(U1-1C)") (class "Default")
      (node (ref "D1") (pin "2") (pinfunction "2_2") (pintype "bidirectional"))
      (node (ref "OF8") (pin "2") (pinfunction "2_2") (pintype "bidirectional"))
      (node (ref "U1") (pin "18") (pinfunction "1C_18") (pintype "output"))
    )
    (net (code "119") (name "Net-(U1-2C)") (class "Default")
      (node (ref "D1") (pin "1") (pinfunction "1_1") (pintype "bidirectional"))
      (node (ref "OF7") (pin "2") (pinfunction "2_2") (pintype "bidirectional"))
      (node (ref "U1") (pin "17") (pinfunction "2C_17") (pintype "output"))
    )
    (net (code "120") (name "Net-(U1-3C)") (class "Default")
      (node (ref "D2") (pin "2") (pinfunction "2_2") (pintype "bidirectional"))
      (node (ref "OF6") (pin "2") (pinfunction "2_2") (pintype "bidirectional"))
      (node (ref "U1") (pin "16") (pinfunction "3C_16") (pintype "output"))
    )
    (net (code "121") (name "Net-(U1-4C)") (class "Default")
      (node (ref "D2") (pin "1") (pinfunction "1_1") (pintype "bidirectional"))
      (node (ref "OF5") (pin "2") (pinfunction "2_2") (pintype "bidirectional"))
      (node (ref "U1") (pin "15") (pinfunction "4C_15") (pintype "output"))
    )
    (net (code "122") (name "Net-(U1-5C)") (class "Default")
      (node (ref "D3") (pin "2") (pinfunction "2_2") (pintype "bidirectional"))
      (node (ref "OF4") (pin "2") (pinfunction "2_2") (pintype "bidirectional"))
      (node (ref "U1") (pin "14") (pinfunction "5C_14") (pintype "output"))
    )
    (net (code "123") (name "Net-(U1-6C)") (class "Default")
      (node (ref "D3") (pin "1") (pinfunction "1_1") (pintype "bidirectional"))
      (node (ref "OF3") (pin "2") (pinfunction "2_2") (pintype "bidirectional"))
      (node (ref "U1") (pin "13") (pinfunction "6C_13") (pintype "output"))
    )
    (net (code "124") (name "Net-(U1-7C)") (class "Default")
      (node (ref "D4") (pin "2") (pinfunction "2_2") (pintype "bidirectional"))
      (node (ref "OF2") (pin "2") (pinfunction "2_2") (pintype "bidirectional"))
      (node (ref "U1") (pin "12") (pinfunction "7C_12") (pintype "output"))
    )
    (net (code "125") (name "Net-(U1-8C)") (class "Default")
      (node (ref "D4") (pin "1") (pinfunction "1_1") (pintype "bidirectional"))
      (node (ref "OF1") (pin "2") (pinfunction "2_2") (pintype "bidirectional"))
      (node (ref "U1") (pin "11") (pinfunction "8C_11") (pintype "output"))
    )
    (net (code "126") (name "Net-(XI1B-SK)") (class "Default")
      (node (ref "IIR1") (pin "1") (pinfunction "1_1") (pintype "passive"))
      (node (ref "XI1") (pin "2") (pinfunction "SK_2") (pintype "passive"))
    )
    (net (code "127") (name "Net-(XI2B-SK)") (class "Default")
      (node (ref "IIR2") (pin "1") (pinfunction "1_1") (pintype "passive"))
      (node (ref "XI2") (pin "2") (pinfunction "SK_2") (pintype "passive"))
    )
    (net (code "128") (name "Net-(XOA-SK)") (class "Default")
      (node (ref "OD1") (pin "A") (pinfunction "A_A") (pintype "passive"))
      (node (ref "XO") (pin "1") (pinfunction "SK_1") (pintype "passive"))
    )
    (net (code "129") (name "Net-(XOB-SK)") (class "Default")
      (node (ref "OF8") (pin "1") (pinfunction "1_1") (pintype "bidirectional"))
      (node (ref "XO") (pin "10") (pinfunction "SK_10") (pintype "passive"))
    )
    (net (code "130") (name "Net-(XOD-SK)") (class "Default")
      (node (ref "OF1") (pin "1") (pinfunction "1_1") (pintype "bidirectional"))
      (node (ref "XO") (pin "3") (pinfunction "SK_3") (pintype "passive"))
    )
    (net (code "131") (name "Net-(XOE-SK)") (class "Default")
      (node (ref "OF2") (pin "1") (pinfunction "1_1") (pintype "bidirectional"))
      (node (ref "XO") (pin "4") (pinfunction "SK_4") (pintype "passive"))
    )
    (net (code "132") (name "Net-(XOF-SK)") (class "Default")
      (node (ref "OF3") (pin "1") (pinfunction "1_1") (pintype "bidirectional"))
      (node (ref "XO") (pin "5") (pinfunction "SK_5") (pintype "passive"))
    )
    (net (code "133") (name "Net-(XOG-SK)") (class "Default")
      (node (ref "OF4") (pin "1") (pinfunction "1_1") (pintype "bidirectional"))
      (node (ref "XO") (pin "6") (pinfunction "SK_6") (pintype "passive"))
    )
    (net (code "134") (name "Net-(XOH-SK)") (class "Default")
      (node (ref "OF5") (pin "1") (pinfunction "1_1") (pintype "bidirectional"))
      (node (ref "XO") (pin "7") (pinfunction "SK_7") (pintype "passive"))
    )
    (net (code "135") (name "Net-(XOI-SK)") (class "Default")
      (node (ref "OF6") (pin "1") (pinfunction "1_1") (pintype "bidirectional"))
      (node (ref "XO") (pin "8") (pinfunction "SK_8") (pintype "passive"))
    )
    (net (code "136") (name "Net-(XOJ-SK)") (class "Default")
      (node (ref "OF7") (pin "1") (pinfunction "1_1") (pintype "bidirectional"))
      (node (ref "XO") (pin "9") (pinfunction "SK_9") (pintype "passive"))
    )
    (net (code "137") (name "OI1") (class "Default")
      (node (ref "OK3") (pin "15") (pinfunction "EMIT_15") (pintype "passive"))
      (node (ref "OR2") (pin "1") (pinfunction "1_1") (pintype "passive"))
      (node (ref "U1") (pin "8") (pinfunction "8B_8") (pintype "input"))
    )
    (net (code "138") (name "OI2") (class "Default")
      (node (ref "OK3") (pin "13") (pinfunction "EMIT_13") (pintype "passive"))
      (node (ref "OR2") (pin "2") (pinfunction "1_2") (pintype "passive"))
      (node (ref "U1") (pin "7") (pinfunction "7B_7") (pintype "input"))
    )
    (net (code "139") (name "OI3") (class "Default")
      (node (ref "OK3") (pin "11") (pinfunction "EMIT_11") (pintype "passive"))
      (node (ref "OR2") (pin "3") (pinfunction "1_3") (pintype "passive"))
      (node (ref "U1") (pin "6") (pinfunction "6B_6") (pintype "input"))
    )
    (net (code "140") (name "OI4") (class "Default")
      (node (ref "OK3") (pin "9") (pinfunction "EMIT_9") (pintype "passive"))
      (node (ref "OR2") (pin "4") (pinfunction "1_4") (pintype "passive"))
      (node (ref "U1") (pin "5") (pinfunction "5B_5") (pintype "input"))
    )
    (net (code "141") (name "RAW_IV") (class "Default")
      (node (ref "GPIO") (pin "1") (pinfunction "S_1") (pintype "passive"))
      (node (ref "PC1") (pin "+") (pinfunction "+_+") (pintype "passive"))
      (node (ref "PF1") (pin "2") (pinfunction "2_2") (pintype "passive"))
      (node (ref "PIC33") (pin "1") (pinfunction "VIN_1") (pintype "input"))
    )
    (net (code "142") (name "RESET") (class "Default")
      (node (ref "BL") (pin "5") (pinfunction "S_5") (pintype "passive"))
      (node (ref "C2") (pin "1") (pinfunction "1_1") (pintype "passive"))
      (node (ref "MC") (pin "29") (pinfunction "PC6(/RESET)_29") (pintype "bidirectional"))
      (node (ref "R2") (pin "1") (pinfunction "1_1") (pintype "passive"))
      (node (ref "SR") (pin "1") (pinfunction "P_1") (pintype "passive"))
    )
    (net (code "143") (name "RXI") (class "Default")
      (node (ref "MC") (pin "30") (pinfunction "PD0(RXD)_30") (pintype "bidirectional"))
      (node (ref "PP") (pin "4") (pinfunction "S_4") (pintype "passive"))
    )
    (net (code "144") (name "TXO") (class "Default")
      (node (ref "MC") (pin "31") (pinfunction "PD1(TXD)_31") (pintype "bidirectional"))
      (node (ref "PP") (pin "3") (pinfunction "S_3") (pintype "passive"))
    )
    (net (code "145") (name "VDDO") (class "Default")
      (node (ref "D1") (pin "3") (pinfunction "3_3") (pintype "bidirectional"))
      (node (ref "D2") (pin "3") (pinfunction "3_3") (pintype "bidirectional"))
      (node (ref "D3") (pin "3") (pinfunction "3_3") (pintype "bidirectional"))
      (node (ref "D4") (pin "3") (pinfunction "3_3") (pintype "bidirectional"))
      (node (ref "EC6") (pin "+") (pinfunction "+_+") (pintype "passive"))
      (node (ref "OD2") (pin "C") (pinfunction "C_C") (pintype "passive"))
      (node (ref "OMF") (pin "1") (pinfunction "1_1") (pintype "bidirectional"))
      (node (ref "OR3") (pin "5") (pinfunction "2_5") (pintype "passive"))
      (node (ref "OR3") (pin "6") (pinfunction "2_6") (pintype "passive"))
      (node (ref "OR3") (pin "7") (pinfunction "2_7") (pintype "passive"))
      (node (ref "OR3") (pin "8") (pinfunction "2_8") (pintype "passive"))
      (node (ref "OR5") (pin "5") (pinfunction "2_5") (pintype "passive"))
      (node (ref "OR5") (pin "6") (pinfunction "2_6") (pintype "passive"))
      (node (ref "OR5") (pin "7") (pinfunction "2_7") (pintype "passive"))
      (node (ref "OR5") (pin "8") (pinfunction "2_8") (pintype "passive"))
      (node (ref "U1") (pin "10") (pinfunction "COM_10") (pintype "output"))
    )
    (net (code "146") (name "VIN") (class "Default")
      (node (ref "PD1") (pin "A") (pinfunction "A_A") (pintype "passive"))
      (node (ref "PJ1") (pin "VIN0") (pinfunction "PWR_VIN0") (pintype "bidirectional"))
      (node (ref "XV") (pin "2") (pinfunction "SK_2") (pintype "passive"))
    )
    (net (code "147") (name "WFGPIO0") (class "Default")
      (node (ref "GPIO") (pin "13") (pinfunction "S_13") (pintype "passive"))
      (node (ref "WIFI") (pin "GPIO0") (pinfunction "GPIO0_GPIO0") (pintype "bidirectional"))
    )
    (net (code "148") (name "WFGPIO2") (class "Default")
      (node (ref "GPIO") (pin "14") (pinfunction "S_14") (pintype "passive"))
      (node (ref "WIFI") (pin "GPIO2") (pinfunction "GPIO2_GPIO2") (pintype "bidirectional"))
    )
    (net (code "149") (name "unconnected-(ENC-CLKOUT-Pad3)") (class "Default")
      (node (ref "ENC") (pin "3") (pinfunction "CLKOUT_3") (pintype "output"))
    )
    (net (code "150") (name "unconnected-(ENC-WOL-Pad5)") (class "Default")
      (node (ref "ENC") (pin "5") (pinfunction "WOL_5") (pintype "output"))
    )
    (net (code "151") (name "unconnected-(IC1-INTA-Pad20)") (class "Default")
      (node (ref "IC1") (pin "20") (pinfunction "INTA_20") (pintype "output"))
    )
    (net (code "152") (name "unconnected-(PJ1-GND-PadP$4)") (class "Default")
      (node (ref "PJ1") (pin "P$4") (pinfunction "GND_P$4") (pintype "bidirectional"))
    )
    (net (code "153") (name "unconnected-(U$2-PadNC)") (class "Default")
      (node (ref "U$2") (pin "NC") (pinfunction "NC_NC") (pintype "bidirectional"))
    )
    (net (code "154") (name "unconnected-(WIFI-PadRST)") (class "Default")
      (node (ref "WIFI") (pin "RST") (pinfunction "RST_RST") (pintype "bidirectional"))
    )
  )
)
